# E4-blackpill-v2.net
KiCad netlist of a schematic drawn in EAGLE
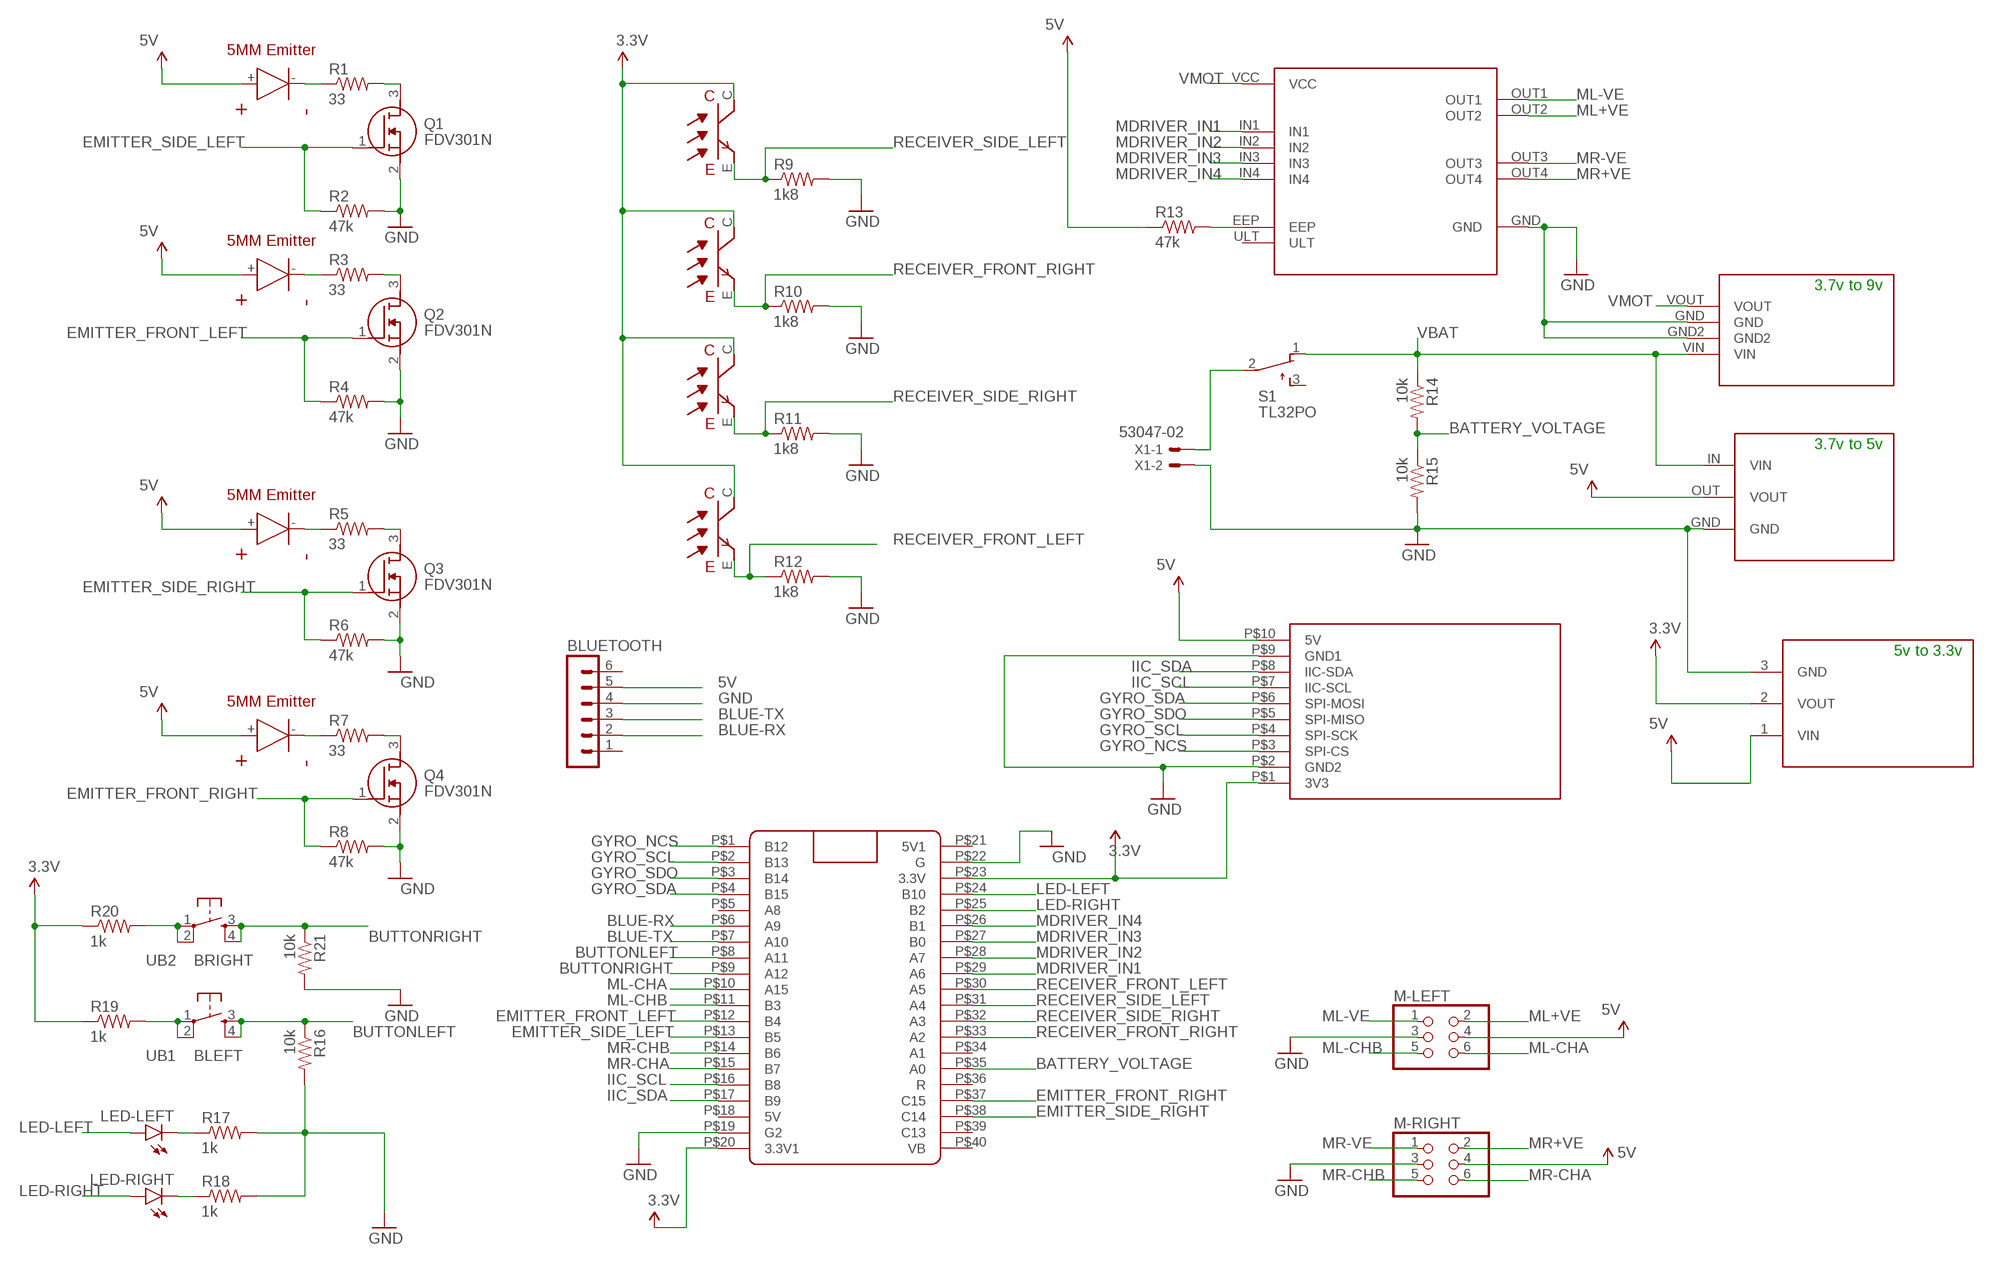
[diagram p0: schematic, sheet 1]

(export (version "E")
  (design (tool "Eeschema 10.0.6"))
  (components
    (comp (ref "BLUETOOTH")
      (value "MA06-1")
      (footprint "eagle-import:MA06-1")
      (libsource (lib "eagle-import") (part "MA06-1"))
    )
    (comp (ref "DET-FRONTLEFT")
      (value "RECEIVER")
      (footprint "eagle-import:RECEIVER")
      (libsource (lib "eagle-import") (part "RECEIVER"))
    )
    (comp (ref "DET-FRONTRIGHT")
      (value "RECEIVER")
      (footprint "eagle-import:RECEIVER")
      (libsource (lib "eagle-import") (part "RECEIVER"))
    )
    (comp (ref "DET-SIDELEFT")
      (value "RECEIVER")
      (footprint "eagle-import:RECEIVER")
      (libsource (lib "eagle-import") (part "RECEIVER"))
    )
    (comp (ref "DET-SIDERIGHT")
      (value "RECEIVER")
      (footprint "eagle-import:RECEIVER")
      (libsource (lib "eagle-import") (part "RECEIVER"))
    )
    (comp (ref "IR-FRONTLEFT")
      (value "EMITTER")
      (footprint "eagle-import:EMITTER")
      (libsource (lib "eagle-import") (part "EMITTER"))
    )
    (comp (ref "IR-FRONTRIGHT")
      (value "EMITTER")
      (footprint "eagle-import:EMITTER")
      (libsource (lib "eagle-import") (part "EMITTER"))
    )
    (comp (ref "IR-SIDELEFT")
      (value "EMITTER")
      (footprint "eagle-import:EMITTER")
      (libsource (lib "eagle-import") (part "EMITTER"))
    )
    (comp (ref "IR-SIDERIGHT")
      (value "EMITTER")
      (footprint "eagle-import:EMITTER")
      (libsource (lib "eagle-import") (part "EMITTER"))
    )
    (comp (ref "LED-LEFT")
      (value "LEDSML0603")
      (footprint "eagle-import:SML0603")
      (libsource (lib "eagle-import") (part "LEDSML0603"))
    )
    (comp (ref "LED-RIGHT")
      (value "LEDSML0603")
      (footprint "eagle-import:SML0603")
      (libsource (lib "eagle-import") (part "LEDSML0603"))
    )
    (comp (ref "M-LEFT")
      (value "PINHD-2X3")
      (footprint "eagle-import:2X03")
      (libsource (lib "eagle-import") (part "PINHD-2X3"))
    )
    (comp (ref "M-RIGHT")
      (value "PINHD-2X3")
      (footprint "eagle-import:2X03")
      (libsource (lib "eagle-import") (part "PINHD-2X3"))
    )
    (comp (ref "Q1")
      (value "FDV301N")
      (footprint "eagle-import:SOT96P237X111-3N")
      (fields (field (name "MOUSER_PART_NUMBER") "512-FDV301N"))
      (libsource (lib "eagle-import") (part "FDV301N"))
    )
    (comp (ref "Q2")
      (value "FDV301N")
      (footprint "eagle-import:SOT96P237X111-3N")
      (fields (field (name "MOUSER_PART_NUMBER") "512-FDV301N"))
      (libsource (lib "eagle-import") (part "FDV301N"))
    )
    (comp (ref "Q3")
      (value "FDV301N")
      (footprint "eagle-import:SOT96P237X111-3N")
      (fields (field (name "MOUSER_PART_NUMBER") "512-FDV301N"))
      (libsource (lib "eagle-import") (part "FDV301N"))
    )
    (comp (ref "Q4")
      (value "FDV301N")
      (footprint "eagle-import:SOT96P237X111-3N")
      (fields (field (name "MOUSER_PART_NUMBER") "512-FDV301N"))
      (libsource (lib "eagle-import") (part "FDV301N"))
    )
    (comp (ref "R1")
      (value "33")
      (footprint "eagle-import:1206")
      (libsource (lib "eagle-import") (part "RESISTOR1206"))
    )
    (comp (ref "R2")
      (value "47k")
      (footprint "eagle-import:0603-RES")
      (libsource (lib "eagle-import") (part "RESISTOR0603-RES"))
    )
    (comp (ref "R3")
      (value "33")
      (footprint "eagle-import:1206")
      (libsource (lib "eagle-import") (part "RESISTOR1206"))
    )
    (comp (ref "R4")
      (value "47k")
      (footprint "eagle-import:0603-RES")
      (libsource (lib "eagle-import") (part "RESISTOR0603-RES"))
    )
    (comp (ref "R5")
      (value "33")
      (footprint "eagle-import:1206")
      (libsource (lib "eagle-import") (part "RESISTOR1206"))
    )
    (comp (ref "R6")
      (value "47k")
      (footprint "eagle-import:0603-RES")
      (libsource (lib "eagle-import") (part "RESISTOR0603-RES"))
    )
    (comp (ref "R7")
      (value "33")
      (footprint "eagle-import:1206")
      (libsource (lib "eagle-import") (part "RESISTOR1206"))
    )
    (comp (ref "R8")
      (value "47k")
      (footprint "eagle-import:0603-RES")
      (libsource (lib "eagle-import") (part "RESISTOR0603-RES"))
    )
    (comp (ref "R9")
      (value "1k8")
      (footprint "eagle-import:0603-RES")
      (libsource (lib "eagle-import") (part "RESISTOR0603-RES"))
    )
    (comp (ref "R10")
      (value "1k8")
      (footprint "eagle-import:0603-RES")
      (libsource (lib "eagle-import") (part "RESISTOR0603-RES"))
    )
    (comp (ref "R11")
      (value "1k8")
      (footprint "eagle-import:0603-RES")
      (libsource (lib "eagle-import") (part "RESISTOR0603-RES"))
    )
    (comp (ref "R12")
      (value "1k8")
      (footprint "eagle-import:0603-RES")
      (libsource (lib "eagle-import") (part "RESISTOR0603-RES"))
    )
    (comp (ref "R13")
      (value "47k")
      (footprint "eagle-import:0603-RES")
      (libsource (lib "eagle-import") (part "RESISTOR0603-RES"))
    )
    (comp (ref "R14")
      (value "10k")
      (footprint "eagle-import:0603-RES")
      (libsource (lib "eagle-import") (part "RESISTOR0603-RES"))
    )
    (comp (ref "R15")
      (value "10k")
      (footprint "eagle-import:0603-RES")
      (libsource (lib "eagle-import") (part "RESISTOR0603-RES"))
    )
    (comp (ref "R16")
      (value "10k")
      (footprint "eagle-import:0603-RES")
      (libsource (lib "eagle-import") (part "RESISTOR0603-RES"))
    )
    (comp (ref "R17")
      (value "1k")
      (footprint "eagle-import:0603-RES")
      (libsource (lib "eagle-import") (part "RESISTOR0603-RES"))
    )
    (comp (ref "R18")
      (value "1k")
      (footprint "eagle-import:0603-RES")
      (libsource (lib "eagle-import") (part "RESISTOR0603-RES"))
    )
    (comp (ref "R19")
      (value "1k")
      (footprint "eagle-import:0603-RES")
      (libsource (lib "eagle-import") (part "RESISTOR0603-RES"))
    )
    (comp (ref "R20")
      (value "1k")
      (footprint "eagle-import:0603-RES")
      (libsource (lib "eagle-import") (part "RESISTOR0603-RES"))
    )
    (comp (ref "R21")
      (value "10k")
      (footprint "eagle-import:0603-RES")
      (libsource (lib "eagle-import") (part "RESISTOR0603-RES"))
    )
    (comp (ref "S1")
      (value "TL32PO")
      (footprint "eagle-import:TL3XPO")
      (libsource (lib "eagle-import") (part "TL32PO"))
    )
    (comp (ref "U$1")
      (value "E4_SPI-IIC")
      (footprint "eagle-import:E4_SPI-IIC")
      (libsource (lib "eagle-import") (part "E4_SPI-IIC"))
    )
    (comp (ref "U$3")
      (value "DRV8833")
      (footprint "eagle-import:DRV8833")
      (libsource (lib "eagle-import") (part "DRV8833"))
    )
    (comp (ref "U$4")
      (value "BUCK3TO9BUCK3TO9-HORIZONTAL")
      (footprint "eagle-import:BUCK3TO9-HORIZONTAL")
      (libsource (lib "eagle-import") (part "BUCK3TO9BUCK3TO9-HORIZONTAL"))
    )
    (comp (ref "U$5")
      (value "BUCK3TO5")
      (footprint "eagle-import:BUCK3TO5-H")
      (libsource (lib "eagle-import") (part "BUCK3TO5"))
    )
    (comp (ref "U$7")
      (value "BLACK_PILL")
      (footprint "eagle-import:BLACK_PILL")
      (libsource (lib "eagle-import") (part "BLACK_PILL"))
    )
    (comp (ref "U$8")
      (value "3V3-CONV3V3CONV")
      (footprint "eagle-import:6410-03")
      (libsource (lib "eagle-import") (part "3V3-CONV3V3CONV"))
    )
    (comp (ref "UB1")
      (value "BLEFT")
      (footprint "eagle-import:TACTILE-PTH")
      (libsource (lib "eagle-import") (part "TAC_SWITCHPTH"))
    )
    (comp (ref "UB2")
      (value "BRIGHT")
      (footprint "eagle-import:TACTILE-PTH")
      (libsource (lib "eagle-import") (part "TAC_SWITCHPTH"))
    )
    (comp (ref "X1")
      (value "53047-02")
      (footprint "eagle-import:53047-02")
      (fields (field (name "MF") "MOLEX") (field (name "MPN") "53047-0210"))
      (libsource (lib "eagle-import") (part "53?-02047"))
    )
  )
  (nets
    (net (code "1") (name "/5V1") (class "Default")
      (node (ref "U$7") (pin "P$21") (pinfunction "5V1_P$21") (pintype "power_in"))
    )
    (net (code "2") (name "/BATTERY_VOLTAGE") (class "Default")
      (node (ref "R14") (pin "2") (pinfunction "2_2") (pintype "passive"))
      (node (ref "R15") (pin "1") (pinfunction "1_1") (pintype "passive"))
      (node (ref "U$7") (pin "P$35") (pinfunction "A0_P$35") (pintype "bidirectional"))
    )
    (net (code "3") (name "/BLUE-RX") (class "Default")
      (node (ref "BLUETOOTH") (pin "2") (pinfunction "2_2") (pintype "passive"))
      (node (ref "U$7") (pin "P$6") (pinfunction "A9_P$6") (pintype "bidirectional"))
    )
    (net (code "4") (name "/BLUE-TX") (class "Default")
      (node (ref "BLUETOOTH") (pin "3") (pinfunction "3_3") (pintype "passive"))
      (node (ref "U$7") (pin "P$7") (pinfunction "A10_P$7") (pintype "bidirectional"))
    )
    (net (code "5") (name "/BUTTONLEFT") (class "Default")
      (node (ref "R16") (pin "1") (pinfunction "1_1") (pintype "passive"))
      (node (ref "U$7") (pin "P$8") (pinfunction "A11_P$8") (pintype "bidirectional"))
      (node (ref "UB1") (pin "3") (pinfunction "3_3") (pintype "passive"))
      (node (ref "UB1") (pin "4") (pinfunction "4_4") (pintype "passive"))
    )
    (net (code "6") (name "/BUTTONRIGHT") (class "Default")
      (node (ref "R21") (pin "1") (pinfunction "1_1") (pintype "passive"))
      (node (ref "U$7") (pin "P$9") (pinfunction "A12_P$9") (pintype "bidirectional"))
      (node (ref "UB2") (pin "3") (pinfunction "3_3") (pintype "passive"))
      (node (ref "UB2") (pin "4") (pinfunction "4_4") (pintype "passive"))
    )
    (net (code "7") (name "/EMITTER_FRONT_LEFT") (class "Default")
      (node (ref "Q2") (pin "1") (pinfunction "G_1") (pintype "bidirectional"))
      (node (ref "R4") (pin "1") (pinfunction "1_1") (pintype "passive"))
      (node (ref "U$7") (pin "P$12") (pinfunction "B4_P$12") (pintype "bidirectional"))
    )
    (net (code "8") (name "/EMITTER_FRONT_RIGHT") (class "Default")
      (node (ref "Q4") (pin "1") (pinfunction "G_1") (pintype "bidirectional"))
      (node (ref "R8") (pin "1") (pinfunction "1_1") (pintype "passive"))
      (node (ref "U$7") (pin "P$37") (pinfunction "C15_P$37") (pintype "bidirectional"))
    )
    (net (code "9") (name "/EMITTER_SIDE_LEFT") (class "Default")
      (node (ref "Q1") (pin "1") (pinfunction "G_1") (pintype "bidirectional"))
      (node (ref "R2") (pin "1") (pinfunction "1_1") (pintype "passive"))
      (node (ref "U$7") (pin "P$13") (pinfunction "B5_P$13") (pintype "bidirectional"))
    )
    (net (code "10") (name "/EMITTER_SIDE_RIGHT") (class "Default")
      (node (ref "Q3") (pin "1") (pinfunction "G_1") (pintype "bidirectional"))
      (node (ref "R6") (pin "1") (pinfunction "1_1") (pintype "passive"))
      (node (ref "U$7") (pin "P$38") (pinfunction "C14_P$38") (pintype "bidirectional"))
    )
    (net (code "11") (name "/GYRO_NCS") (class "Default")
      (node (ref "U$1") (pin "P$3") (pinfunction "SPI-CS_P$3") (pintype "bidirectional"))
      (node (ref "U$7") (pin "P$1") (pinfunction "B12_P$1") (pintype "bidirectional"))
    )
    (net (code "12") (name "/GYRO_SCL") (class "Default")
      (node (ref "U$1") (pin "P$4") (pinfunction "SPI-SCK_P$4") (pintype "bidirectional"))
      (node (ref "U$7") (pin "P$2") (pinfunction "B13_P$2") (pintype "bidirectional"))
    )
    (net (code "13") (name "/GYRO_SDA") (class "Default")
      (node (ref "U$1") (pin "P$6") (pinfunction "SPI-MOSI_P$6") (pintype "bidirectional"))
      (node (ref "U$7") (pin "P$4") (pinfunction "B15_P$4") (pintype "bidirectional"))
    )
    (net (code "14") (name "/GYRO_SDO") (class "Default")
      (node (ref "U$1") (pin "P$5") (pinfunction "SPI-MISO_P$5") (pintype "bidirectional"))
      (node (ref "U$7") (pin "P$3") (pinfunction "B14_P$3") (pintype "bidirectional"))
    )
    (net (code "15") (name "/IIC_SCL") (class "Default")
      (node (ref "U$1") (pin "P$7") (pinfunction "IIC-SCL_P$7") (pintype "bidirectional"))
      (node (ref "U$7") (pin "P$16") (pinfunction "B8_P$16") (pintype "bidirectional"))
    )
    (net (code "16") (name "/IIC_SDA") (class "Default")
      (node (ref "U$1") (pin "P$8") (pinfunction "IIC-SDA_P$8") (pintype "bidirectional"))
      (node (ref "U$7") (pin "P$17") (pinfunction "B9_P$17") (pintype "bidirectional"))
    )
    (net (code "17") (name "/LED-LEFT") (class "Default")
      (node (ref "LED-LEFT") (pin "A") (pinfunction "A_A") (pintype "passive"))
      (node (ref "U$7") (pin "P$24") (pinfunction "B10_P$24") (pintype "bidirectional"))
    )
    (net (code "18") (name "/LED-RIGHT") (class "Default")
      (node (ref "LED-RIGHT") (pin "A") (pinfunction "A_A") (pintype "passive"))
      (node (ref "U$7") (pin "P$25") (pinfunction "B2_P$25") (pintype "bidirectional"))
    )
    (net (code "19") (name "/MDRIVER_IN1") (class "Default")
      (node (ref "U$3") (pin "IN1") (pinfunction "IN1_IN1") (pintype "bidirectional"))
      (node (ref "U$7") (pin "P$29") (pinfunction "A6_P$29") (pintype "bidirectional"))
    )
    (net (code "20") (name "/MDRIVER_IN2") (class "Default")
      (node (ref "U$3") (pin "IN2") (pinfunction "IN2_IN2") (pintype "bidirectional"))
      (node (ref "U$7") (pin "P$28") (pinfunction "A7_P$28") (pintype "bidirectional"))
    )
    (net (code "21") (name "/MDRIVER_IN3") (class "Default")
      (node (ref "U$3") (pin "IN3") (pinfunction "IN3_IN3") (pintype "bidirectional"))
      (node (ref "U$7") (pin "P$27") (pinfunction "B0_P$27") (pintype "bidirectional"))
    )
    (net (code "22") (name "/MDRIVER_IN4") (class "Default")
      (node (ref "U$3") (pin "IN4") (pinfunction "IN4_IN4") (pintype "bidirectional"))
      (node (ref "U$7") (pin "P$26") (pinfunction "B1_P$26") (pintype "bidirectional"))
    )
    (net (code "23") (name "/ML+VE") (class "Default")
      (node (ref "M-LEFT") (pin "2") (pinfunction "2_2") (pintype "passive"))
      (node (ref "U$3") (pin "OUT2") (pinfunction "OUT2_OUT2") (pintype "bidirectional"))
    )
    (net (code "24") (name "/ML-CHA") (class "Default")
      (node (ref "M-LEFT") (pin "6") (pinfunction "6_6") (pintype "passive"))
      (node (ref "U$7") (pin "P$10") (pinfunction "A15_P$10") (pintype "bidirectional"))
    )
    (net (code "25") (name "/ML-CHB") (class "Default")
      (node (ref "M-LEFT") (pin "5") (pinfunction "5_5") (pintype "passive"))
      (node (ref "U$7") (pin "P$11") (pinfunction "B3_P$11") (pintype "bidirectional"))
    )
    (net (code "26") (name "/ML-VE") (class "Default")
      (node (ref "M-LEFT") (pin "1") (pinfunction "1_1") (pintype "passive"))
      (node (ref "U$3") (pin "OUT1") (pinfunction "OUT1_OUT1") (pintype "bidirectional"))
    )
    (net (code "27") (name "/MR+VE") (class "Default")
      (node (ref "M-RIGHT") (pin "2") (pinfunction "2_2") (pintype "passive"))
      (node (ref "U$3") (pin "OUT4") (pinfunction "OUT4_OUT4") (pintype "bidirectional"))
    )
    (net (code "28") (name "/MR-CHA") (class "Default")
      (node (ref "M-RIGHT") (pin "6") (pinfunction "6_6") (pintype "passive"))
      (node (ref "U$7") (pin "P$15") (pinfunction "B7_P$15") (pintype "bidirectional"))
    )
    (net (code "29") (name "/MR-CHB") (class "Default")
      (node (ref "M-RIGHT") (pin "5") (pinfunction "5_5") (pintype "passive"))
      (node (ref "U$7") (pin "P$14") (pinfunction "B6_P$14") (pintype "bidirectional"))
    )
    (net (code "30") (name "/MR-VE") (class "Default")
      (node (ref "M-RIGHT") (pin "1") (pinfunction "1_1") (pintype "passive"))
      (node (ref "U$3") (pin "OUT3") (pinfunction "OUT3_OUT3") (pintype "bidirectional"))
    )
    (net (code "31") (name "/RECEIVER_FRONT_LEFT") (class "Default")
      (node (ref "DET-FRONTLEFT") (pin "E") (pinfunction "E_E") (pintype "bidirectional"))
      (node (ref "R12") (pin "1") (pinfunction "1_1") (pintype "passive"))
      (node (ref "U$7") (pin "P$30") (pinfunction "A5_P$30") (pintype "bidirectional"))
    )
    (net (code "32") (name "/RECEIVER_FRONT_RIGHT") (class "Default")
      (node (ref "DET-FRONTRIGHT") (pin "E") (pinfunction "E_E") (pintype "bidirectional"))
      (node (ref "R10") (pin "1") (pinfunction "1_1") (pintype "passive"))
      (node (ref "U$7") (pin "P$33") (pinfunction "A2_P$33") (pintype "bidirectional"))
    )
    (net (code "33") (name "/RECEIVER_SIDE_LEFT") (class "Default")
      (node (ref "DET-SIDELEFT") (pin "E") (pinfunction "E_E") (pintype "bidirectional"))
      (node (ref "R9") (pin "1") (pinfunction "1_1") (pintype "passive"))
      (node (ref "U$7") (pin "P$31") (pinfunction "A4_P$31") (pintype "bidirectional"))
    )
    (net (code "34") (name "/RECEIVER_SIDE_RIGHT") (class "Default")
      (node (ref "DET-SIDERIGHT") (pin "E") (pinfunction "E_E") (pintype "bidirectional"))
      (node (ref "R11") (pin "1") (pinfunction "1_1") (pintype "passive"))
      (node (ref "U$7") (pin "P$32") (pinfunction "A3_P$32") (pintype "bidirectional"))
    )
    (net (code "35") (name "/VBAT") (class "Default")
      (node (ref "R14") (pin "1") (pinfunction "1_1") (pintype "passive"))
      (node (ref "S1") (pin "1") (pinfunction "O_1") (pintype "passive"))
      (node (ref "U$4") (pin "VIN") (pinfunction "VIN_VIN") (pintype "power_in"))
      (node (ref "U$5") (pin "IN") (pinfunction "VIN_IN") (pintype "power_in"))
    )
    (net (code "36") (name "/VMOT") (class "Default")
      (node (ref "U$3") (pin "VCC") (pinfunction "VCC_VCC") (pintype "power_in"))
      (node (ref "U$4") (pin "VOUT") (pinfunction "VOUT_VOUT") (pintype "power_in"))
    )
    (net (code "37") (name "3.3V") (class "Default")
      (node (ref "DET-FRONTLEFT") (pin "C") (pinfunction "C_C") (pintype "bidirectional"))
      (node (ref "DET-FRONTRIGHT") (pin "C") (pinfunction "C_C") (pintype "bidirectional"))
      (node (ref "DET-SIDELEFT") (pin "C") (pinfunction "C_C") (pintype "bidirectional"))
      (node (ref "DET-SIDERIGHT") (pin "C") (pinfunction "C_C") (pintype "bidirectional"))
      (node (ref "R19") (pin "1") (pinfunction "1_1") (pintype "passive"))
      (node (ref "R20") (pin "1") (pinfunction "1_1") (pintype "passive"))
      (node (ref "U$1") (pin "P$1") (pinfunction "3V3_P$1") (pintype "power_in"))
      (node (ref "U$7") (pin "P$20") (pinfunction "3.3V1_P$20") (pintype "bidirectional"))
      (node (ref "U$7") (pin "P$23") (pinfunction "3.3V_P$23") (pintype "bidirectional"))
      (node (ref "U$8") (pin "2") (pinfunction "VOUT_2") (pintype "power_in"))
    )
    (net (code "38") (name "5V") (class "Default")
      (node (ref "BLUETOOTH") (pin "5") (pinfunction "5_5") (pintype "passive"))
      (node (ref "IR-FRONTLEFT") (pin "+") (pinfunction "+_+") (pintype "bidirectional"))
      (node (ref "IR-FRONTRIGHT") (pin "+") (pinfunction "+_+") (pintype "bidirectional"))
      (node (ref "IR-SIDELEFT") (pin "+") (pinfunction "+_+") (pintype "bidirectional"))
      (node (ref "IR-SIDERIGHT") (pin "+") (pinfunction "+_+") (pintype "bidirectional"))
      (node (ref "M-LEFT") (pin "4") (pinfunction "4_4") (pintype "passive"))
      (node (ref "M-RIGHT") (pin "4") (pinfunction "4_4") (pintype "passive"))
      (node (ref "R13") (pin "1") (pinfunction "1_1") (pintype "passive"))
      (node (ref "U$1") (pin "P$10") (pinfunction "5V_P$10") (pintype "power_in"))
      (node (ref "U$5") (pin "OUT") (pinfunction "VOUT_OUT") (pintype "power_in"))
      (node (ref "U$8") (pin "1") (pinfunction "VIN_1") (pintype "power_in"))
    )
    (net (code "39") (name "GND") (class "Default")
      (node (ref "BLUETOOTH") (pin "4") (pinfunction "4_4") (pintype "passive"))
      (node (ref "M-LEFT") (pin "3") (pinfunction "3_3") (pintype "passive"))
      (node (ref "M-RIGHT") (pin "3") (pinfunction "3_3") (pintype "passive"))
      (node (ref "Q1") (pin "2") (pinfunction "S_2") (pintype "bidirectional"))
      (node (ref "Q2") (pin "2") (pinfunction "S_2") (pintype "bidirectional"))
      (node (ref "Q3") (pin "2") (pinfunction "S_2") (pintype "bidirectional"))
      (node (ref "Q4") (pin "2") (pinfunction "S_2") (pintype "bidirectional"))
      (node (ref "R10") (pin "2") (pinfunction "2_2") (pintype "passive"))
      (node (ref "R11") (pin "2") (pinfunction "2_2") (pintype "passive"))
      (node (ref "R12") (pin "2") (pinfunction "2_2") (pintype "passive"))
      (node (ref "R15") (pin "2") (pinfunction "2_2") (pintype "passive"))
      (node (ref "R16") (pin "2") (pinfunction "2_2") (pintype "passive"))
      (node (ref "R17") (pin "2") (pinfunction "2_2") (pintype "passive"))
      (node (ref "R18") (pin "2") (pinfunction "2_2") (pintype "passive"))
      (node (ref "R2") (pin "2") (pinfunction "2_2") (pintype "passive"))
      (node (ref "R21") (pin "2") (pinfunction "2_2") (pintype "passive"))
      (node (ref "R4") (pin "2") (pinfunction "2_2") (pintype "passive"))
      (node (ref "R6") (pin "2") (pinfunction "2_2") (pintype "passive"))
      (node (ref "R8") (pin "2") (pinfunction "2_2") (pintype "passive"))
      (node (ref "R9") (pin "2") (pinfunction "2_2") (pintype "passive"))
      (node (ref "U$1") (pin "P$2") (pinfunction "GND2_P$2") (pintype "power_in"))
      (node (ref "U$1") (pin "P$9") (pinfunction "GND1_P$9") (pintype "power_in"))
      (node (ref "U$3") (pin "GND") (pinfunction "GND_GND") (pintype "power_in"))
      (node (ref "U$4") (pin "GND") (pinfunction "GND_GND") (pintype "power_in"))
      (node (ref "U$4") (pin "GND2") (pinfunction "GND2_GND2") (pintype "power_in"))
      (node (ref "U$5") (pin "GND") (pinfunction "GND_GND") (pintype "power_in"))
      (node (ref "U$7") (pin "P$19") (pinfunction "G2_P$19") (pintype "bidirectional"))
      (node (ref "U$7") (pin "P$22") (pinfunction "G_P$22") (pintype "bidirectional"))
      (node (ref "U$8") (pin "3") (pinfunction "GND_3") (pintype "power_in"))
      (node (ref "X1") (pin "2") (pinfunction "S_2") (pintype "passive"))
    )
    (net (code "40") (name "Net-(IR-FRONTLEFT-Pad-)") (class "Default")
      (node (ref "IR-FRONTLEFT") (pin "-") (pinfunction "-_-") (pintype "bidirectional"))
      (node (ref "R3") (pin "1") (pinfunction "1_1") (pintype "passive"))
    )
    (net (code "41") (name "Net-(IR-FRONTRIGHT-Pad-)") (class "Default")
      (node (ref "IR-FRONTRIGHT") (pin "-") (pinfunction "-_-") (pintype "bidirectional"))
      (node (ref "R7") (pin "1") (pinfunction "1_1") (pintype "passive"))
    )
    (net (code "42") (name "Net-(IR-SIDELEFT-Pad-)") (class "Default")
      (node (ref "IR-SIDELEFT") (pin "-") (pinfunction "-_-") (pintype "bidirectional"))
      (node (ref "R1") (pin "1") (pinfunction "1_1") (pintype "passive"))
    )
    (net (code "43") (name "Net-(IR-SIDERIGHT-Pad-)") (class "Default")
      (node (ref "IR-SIDERIGHT") (pin "-") (pinfunction "-_-") (pintype "bidirectional"))
      (node (ref "R5") (pin "1") (pinfunction "1_1") (pintype "passive"))
    )
    (net (code "44") (name "Net-(LED-LEFT-PadC)") (class "Default")
      (node (ref "LED-LEFT") (pin "C") (pinfunction "C_C") (pintype "passive"))
      (node (ref "R17") (pin "1") (pinfunction "1_1") (pintype "passive"))
    )
    (net (code "45") (name "Net-(LED-RIGHT-PadC)") (class "Default")
      (node (ref "LED-RIGHT") (pin "C") (pinfunction "C_C") (pintype "passive"))
      (node (ref "R18") (pin "1") (pinfunction "1_1") (pintype "passive"))
    )
    (net (code "46") (name "Net-(Q1-D)") (class "Default")
      (node (ref "Q1") (pin "3") (pinfunction "D_3") (pintype "bidirectional"))
      (node (ref "R1") (pin "2") (pinfunction "2_2") (pintype "passive"))
    )
    (net (code "47") (name "Net-(Q2-D)") (class "Default")
      (node (ref "Q2") (pin "3") (pinfunction "D_3") (pintype "bidirectional"))
      (node (ref "R3") (pin "2") (pinfunction "2_2") (pintype "passive"))
    )
    (net (code "48") (name "Net-(Q3-D)") (class "Default")
      (node (ref "Q3") (pin "3") (pinfunction "D_3") (pintype "bidirectional"))
      (node (ref "R5") (pin "2") (pinfunction "2_2") (pintype "passive"))
    )
    (net (code "49") (name "Net-(Q4-D)") (class "Default")
      (node (ref "Q4") (pin "3") (pinfunction "D_3") (pintype "bidirectional"))
      (node (ref "R7") (pin "2") (pinfunction "2_2") (pintype "passive"))
    )
    (net (code "50") (name "Net-(R13-Pad2)") (class "Default")
      (node (ref "R13") (pin "2") (pinfunction "2_2") (pintype "passive"))
      (node (ref "U$3") (pin "EEP") (pinfunction "EEP_EEP") (pintype "bidirectional"))
    )
    (net (code "51") (name "Net-(R19-Pad2)") (class "Default")
      (node (ref "R19") (pin "2") (pinfunction "2_2") (pintype "passive"))
      (node (ref "UB1") (pin "1") (pinfunction "1_1") (pintype "passive"))
      (node (ref "UB1") (pin "2") (pinfunction "2_2") (pintype "passive"))
    )
    (net (code "52") (name "Net-(R20-Pad2)") (class "Default")
      (node (ref "R20") (pin "2") (pinfunction "2_2") (pintype "passive"))
      (node (ref "UB2") (pin "1") (pinfunction "1_1") (pintype "passive"))
      (node (ref "UB2") (pin "2") (pinfunction "2_2") (pintype "passive"))
    )
    (net (code "53") (name "Net-(S1-P)") (class "Default")
      (node (ref "S1") (pin "2") (pinfunction "P_2") (pintype "passive"))
      (node (ref "X1") (pin "1") (pinfunction "S_1") (pintype "passive"))
    )
    (net (code "54") (name "unconnected-(BLUETOOTH-Pad1)") (class "Default")
      (node (ref "BLUETOOTH") (pin "1") (pinfunction "1_1") (pintype "passive"))
    )
    (net (code "55") (name "unconnected-(BLUETOOTH-Pad6)") (class "Default")
      (node (ref "BLUETOOTH") (pin "6") (pinfunction "6_6") (pintype "passive"))
    )
    (net (code "56") (name "unconnected-(S1-S-Pad3)") (class "Default")
      (node (ref "S1") (pin "3") (pinfunction "S_3") (pintype "passive"))
    )
    (net (code "57") (name "unconnected-(U$3-PadULT)") (class "Default")
      (node (ref "U$3") (pin "ULT") (pinfunction "ULT_ULT") (pintype "bidirectional"))
    )
    (net (code "58") (name "unconnected-(U$7-5V-PadP$18)") (class "Default")
      (node (ref "U$7") (pin "P$18") (pinfunction "5V_P$18") (pintype "bidirectional"))
    )
    (net (code "59") (name "unconnected-(U$7-A1-PadP$34)") (class "Default")
      (node (ref "U$7") (pin "P$34") (pinfunction "A1_P$34") (pintype "bidirectional"))
    )
    (net (code "60") (name "unconnected-(U$7-A8-PadP$5)") (class "Default")
      (node (ref "U$7") (pin "P$5") (pinfunction "A8_P$5") (pintype "bidirectional"))
    )
    (net (code "61") (name "unconnected-(U$7-C13-PadP$39)") (class "Default")
      (node (ref "U$7") (pin "P$39") (pinfunction "C13_P$39") (pintype "bidirectional"))
    )
    (net (code "62") (name "unconnected-(U$7-R-PadP$36)") (class "Default")
      (node (ref "U$7") (pin "P$36") (pinfunction "R_P$36") (pintype "bidirectional"))
    )
    (net (code "63") (name "unconnected-(U$7-VB-PadP$40)") (class "Default")
      (node (ref "U$7") (pin "P$40") (pinfunction "VB_P$40") (pintype "bidirectional"))
    )
  )
)
